# LED.net
KiCad netlist of a schematic drawn in Altium Designer
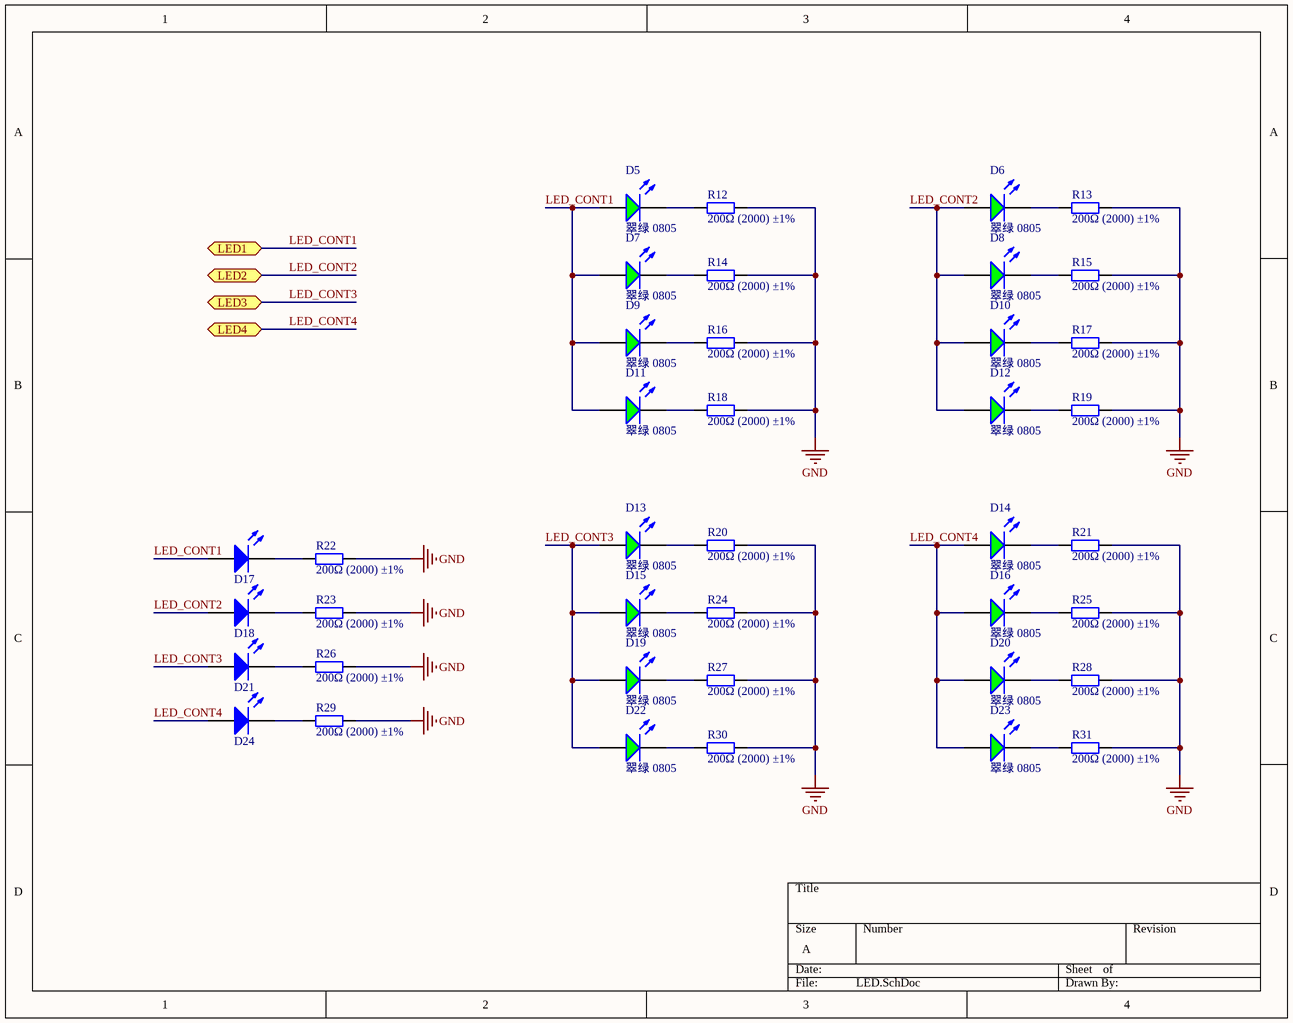
[diagram p0: LED.SchDoc]

(export (version "E")
  (design (tool "Eeschema 10.0.6"))
  (components
    (comp (ref "D5")
      (value "翠绿 0805")
      (footprint "LC-0805_LED_S1")
      (description "发光二极管")
      (libsource (lib "Miscellaneous Devices LC") (part "0805 翠绿"))
    )
    (comp (ref "D6")
      (value "翠绿 0805")
      (footprint "LC-0805_LED_S1")
      (description "发光二极管")
      (libsource (lib "Miscellaneous Devices LC") (part "0805 翠绿"))
    )
    (comp (ref "D7")
      (value "翠绿 0805")
      (footprint "LC-0805_LED_S1")
      (description "发光二极管")
      (libsource (lib "Miscellaneous Devices LC") (part "0805 翠绿"))
    )
    (comp (ref "D8")
      (value "翠绿 0805")
      (footprint "LC-0805_LED_S1")
      (description "发光二极管")
      (libsource (lib "Miscellaneous Devices LC") (part "0805 翠绿"))
    )
    (comp (ref "D9")
      (value "翠绿 0805")
      (footprint "LC-0805_LED_S1")
      (description "发光二极管")
      (libsource (lib "Miscellaneous Devices LC") (part "0805 翠绿"))
    )
    (comp (ref "D10")
      (value "翠绿 0805")
      (footprint "LC-0805_LED_S1")
      (description "发光二极管")
      (libsource (lib "Miscellaneous Devices LC") (part "0805 翠绿"))
    )
    (comp (ref "D11")
      (value "翠绿 0805")
      (footprint "LC-0805_LED_S1")
      (description "发光二极管")
      (libsource (lib "Miscellaneous Devices LC") (part "0805 翠绿"))
    )
    (comp (ref "D12")
      (value "翠绿 0805")
      (footprint "LC-0805_LED_S1")
      (description "发光二极管")
      (libsource (lib "Miscellaneous Devices LC") (part "0805 翠绿"))
    )
    (comp (ref "D13")
      (value "翠绿 0805")
      (footprint "LC-0805_LED_S1")
      (description "发光二极管")
      (libsource (lib "Miscellaneous Devices LC") (part "0805 翠绿"))
    )
    (comp (ref "D14")
      (value "翠绿 0805")
      (footprint "LC-0805_LED_S1")
      (description "发光二极管")
      (libsource (lib "Miscellaneous Devices LC") (part "0805 翠绿"))
    )
    (comp (ref "D15")
      (value "翠绿 0805")
      (footprint "LC-0805_LED_S1")
      (description "发光二极管")
      (libsource (lib "Miscellaneous Devices LC") (part "0805 翠绿"))
    )
    (comp (ref "D16")
      (value "翠绿 0805")
      (footprint "LC-0805_LED_S1")
      (description "发光二极管")
      (libsource (lib "Miscellaneous Devices LC") (part "0805 翠绿"))
    )
    (comp (ref "D17")
      (value "LED0")
      (footprint "LED_A2")
      (description "发光二极管")
      (fields (field (name "PUBLISHER") "Altium Limited"))
      (libsource (lib "Fszhang") (part "LED0"))
    )
    (comp (ref "D18")
      (value "LED0")
      (footprint "LED_A2")
      (description "发光二极管")
      (fields (field (name "PUBLISHER") "Altium Limited"))
      (libsource (lib "Fszhang") (part "LED0"))
    )
    (comp (ref "D19")
      (value "翠绿 0805")
      (footprint "LC-0805_LED_S1")
      (description "发光二极管")
      (libsource (lib "Miscellaneous Devices LC") (part "0805 翠绿"))
    )
    (comp (ref "D20")
      (value "翠绿 0805")
      (footprint "LC-0805_LED_S1")
      (description "发光二极管")
      (libsource (lib "Miscellaneous Devices LC") (part "0805 翠绿"))
    )
    (comp (ref "D21")
      (value "LED0")
      (footprint "LED_A2")
      (description "发光二极管")
      (fields (field (name "PUBLISHER") "Altium Limited"))
      (libsource (lib "Fszhang") (part "LED0"))
    )
    (comp (ref "D22")
      (value "翠绿 0805")
      (footprint "LC-0805_LED_S1")
      (description "发光二极管")
      (libsource (lib "Miscellaneous Devices LC") (part "0805 翠绿"))
    )
    (comp (ref "D23")
      (value "翠绿 0805")
      (footprint "LC-0805_LED_S1")
      (description "发光二极管")
      (libsource (lib "Miscellaneous Devices LC") (part "0805 翠绿"))
    )
    (comp (ref "D24")
      (value "LED0")
      (footprint "LED_A2")
      (description "发光二极管")
      (fields (field (name "PUBLISHER") "Altium Limited"))
      (libsource (lib "Fszhang") (part "LED0"))
    )
    (comp (ref "R12")
      (value "200Ω (2000) ±1%")
      (footprint "LC-0805_R")
      (description "贴片电阻")
      (libsource (lib "Miscellaneous Devices LC") (part "0805 200Ω (2000) 1%"))
    )
    (comp (ref "R13")
      (value "200Ω (2000) ±1%")
      (footprint "LC-0805_R")
      (description "贴片电阻")
      (libsource (lib "Miscellaneous Devices LC") (part "0805 200Ω (2000) 1%"))
    )
    (comp (ref "R14")
      (value "200Ω (2000) ±1%")
      (footprint "LC-0805_R")
      (description "贴片电阻")
      (libsource (lib "Miscellaneous Devices LC") (part "0805 200Ω (2000) 1%"))
    )
    (comp (ref "R15")
      (value "200Ω (2000) ±1%")
      (footprint "LC-0805_R")
      (description "贴片电阻")
      (libsource (lib "Miscellaneous Devices LC") (part "0805 200Ω (2000) 1%"))
    )
    (comp (ref "R16")
      (value "200Ω (2000) ±1%")
      (footprint "LC-0805_R")
      (description "贴片电阻")
      (libsource (lib "Miscellaneous Devices LC") (part "0805 200Ω (2000) 1%"))
    )
    (comp (ref "R17")
      (value "200Ω (2000) ±1%")
      (footprint "LC-0805_R")
      (description "贴片电阻")
      (libsource (lib "Miscellaneous Devices LC") (part "0805 200Ω (2000) 1%"))
    )
    (comp (ref "R18")
      (value "200Ω (2000) ±1%")
      (footprint "LC-0805_R")
      (description "贴片电阻")
      (libsource (lib "Miscellaneous Devices LC") (part "0805 200Ω (2000) 1%"))
    )
    (comp (ref "R19")
      (value "200Ω (2000) ±1%")
      (footprint "LC-0805_R")
      (description "贴片电阻")
      (libsource (lib "Miscellaneous Devices LC") (part "0805 200Ω (2000) 1%"))
    )
    (comp (ref "R20")
      (value "200Ω (2000) ±1%")
      (footprint "LC-0805_R")
      (description "贴片电阻")
      (libsource (lib "Miscellaneous Devices LC") (part "0805 200Ω (2000) 1%"))
    )
    (comp (ref "R21")
      (value "200Ω (2000) ±1%")
      (footprint "LC-0805_R")
      (description "贴片电阻")
      (libsource (lib "Miscellaneous Devices LC") (part "0805 200Ω (2000) 1%"))
    )
    (comp (ref "R22")
      (value "200Ω (2000) ±1%")
      (footprint "LC-0805_R")
      (description "贴片电阻")
      (libsource (lib "Miscellaneous Devices LC") (part "0805 200Ω (2000) 1%"))
    )
    (comp (ref "R23")
      (value "200Ω (2000) ±1%")
      (footprint "LC-0805_R")
      (description "贴片电阻")
      (libsource (lib "Miscellaneous Devices LC") (part "0805 200Ω (2000) 1%"))
    )
    (comp (ref "R24")
      (value "200Ω (2000) ±1%")
      (footprint "LC-0805_R")
      (description "贴片电阻")
      (libsource (lib "Miscellaneous Devices LC") (part "0805 200Ω (2000) 1%"))
    )
    (comp (ref "R25")
      (value "200Ω (2000) ±1%")
      (footprint "LC-0805_R")
      (description "贴片电阻")
      (libsource (lib "Miscellaneous Devices LC") (part "0805 200Ω (2000) 1%"))
    )
    (comp (ref "R26")
      (value "200Ω (2000) ±1%")
      (footprint "LC-0805_R")
      (description "贴片电阻")
      (libsource (lib "Miscellaneous Devices LC") (part "0805 200Ω (2000) 1%"))
    )
    (comp (ref "R27")
      (value "200Ω (2000) ±1%")
      (footprint "LC-0805_R")
      (description "贴片电阻")
      (libsource (lib "Miscellaneous Devices LC") (part "0805 200Ω (2000) 1%"))
    )
    (comp (ref "R28")
      (value "200Ω (2000) ±1%")
      (footprint "LC-0805_R")
      (description "贴片电阻")
      (libsource (lib "Miscellaneous Devices LC") (part "0805 200Ω (2000) 1%"))
    )
    (comp (ref "R29")
      (value "200Ω (2000) ±1%")
      (footprint "LC-0805_R")
      (description "贴片电阻")
      (libsource (lib "Miscellaneous Devices LC") (part "0805 200Ω (2000) 1%"))
    )
    (comp (ref "R30")
      (value "200Ω (2000) ±1%")
      (footprint "LC-0805_R")
      (description "贴片电阻")
      (libsource (lib "Miscellaneous Devices LC") (part "0805 200Ω (2000) 1%"))
    )
    (comp (ref "R31")
      (value "200Ω (2000) ±1%")
      (footprint "LC-0805_R")
      (description "贴片电阻")
      (libsource (lib "Miscellaneous Devices LC") (part "0805 200Ω (2000) 1%"))
    )
  )
  (nets
    (net (code "1") (name "/LED_CONT1") (class "Default")
      (node (ref "D11") (pin "A") (pinfunction "A_A") (pintype "passive"))
      (node (ref "D17") (pin "1") (pinfunction "A_1") (pintype "passive"))
      (node (ref "D5") (pin "A") (pinfunction "A_A") (pintype "passive"))
      (node (ref "D7") (pin "A") (pinfunction "A_A") (pintype "passive"))
      (node (ref "D9") (pin "A") (pinfunction "A_A") (pintype "passive"))
    )
    (net (code "2") (name "/LED_CONT2") (class "Default")
      (node (ref "D10") (pin "A") (pinfunction "A_A") (pintype "passive"))
      (node (ref "D12") (pin "A") (pinfunction "A_A") (pintype "passive"))
      (node (ref "D18") (pin "1") (pinfunction "A_1") (pintype "passive"))
      (node (ref "D6") (pin "A") (pinfunction "A_A") (pintype "passive"))
      (node (ref "D8") (pin "A") (pinfunction "A_A") (pintype "passive"))
    )
    (net (code "3") (name "/LED_CONT3") (class "Default")
      (node (ref "D13") (pin "A") (pinfunction "A_A") (pintype "passive"))
      (node (ref "D15") (pin "A") (pinfunction "A_A") (pintype "passive"))
      (node (ref "D19") (pin "A") (pinfunction "A_A") (pintype "passive"))
      (node (ref "D21") (pin "1") (pinfunction "A_1") (pintype "passive"))
      (node (ref "D22") (pin "A") (pinfunction "A_A") (pintype "passive"))
    )
    (net (code "4") (name "/LED_CONT4") (class "Default")
      (node (ref "D14") (pin "A") (pinfunction "A_A") (pintype "passive"))
      (node (ref "D16") (pin "A") (pinfunction "A_A") (pintype "passive"))
      (node (ref "D20") (pin "A") (pinfunction "A_A") (pintype "passive"))
      (node (ref "D23") (pin "A") (pinfunction "A_A") (pintype "passive"))
      (node (ref "D24") (pin "1") (pinfunction "A_1") (pintype "passive"))
    )
    (net (code "5") (name "GND") (class "Default")
      (node (ref "R12") (pin "2") (pinfunction "2_2") (pintype "passive"))
      (node (ref "R13") (pin "2") (pinfunction "2_2") (pintype "passive"))
      (node (ref "R14") (pin "2") (pinfunction "2_2") (pintype "passive"))
      (node (ref "R15") (pin "2") (pinfunction "2_2") (pintype "passive"))
      (node (ref "R16") (pin "2") (pinfunction "2_2") (pintype "passive"))
      (node (ref "R17") (pin "2") (pinfunction "2_2") (pintype "passive"))
      (node (ref "R18") (pin "2") (pinfunction "2_2") (pintype "passive"))
      (node (ref "R19") (pin "2") (pinfunction "2_2") (pintype "passive"))
      (node (ref "R20") (pin "2") (pinfunction "2_2") (pintype "passive"))
      (node (ref "R21") (pin "2") (pinfunction "2_2") (pintype "passive"))
      (node (ref "R22") (pin "2") (pinfunction "2_2") (pintype "passive"))
      (node (ref "R23") (pin "2") (pinfunction "2_2") (pintype "passive"))
      (node (ref "R24") (pin "2") (pinfunction "2_2") (pintype "passive"))
      (node (ref "R25") (pin "2") (pinfunction "2_2") (pintype "passive"))
      (node (ref "R26") (pin "2") (pinfunction "2_2") (pintype "passive"))
      (node (ref "R27") (pin "2") (pinfunction "2_2") (pintype "passive"))
      (node (ref "R28") (pin "2") (pinfunction "2_2") (pintype "passive"))
      (node (ref "R29") (pin "2") (pinfunction "2_2") (pintype "passive"))
      (node (ref "R30") (pin "2") (pinfunction "2_2") (pintype "passive"))
      (node (ref "R31") (pin "2") (pinfunction "2_2") (pintype "passive"))
    )
    (net (code "6") (name "Net-(D5-PadK)") (class "Default")
      (node (ref "D5") (pin "K") (pinfunction "K_K") (pintype "passive"))
      (node (ref "R12") (pin "1") (pinfunction "1_1") (pintype "passive"))
    )
    (net (code "7") (name "Net-(D6-PadK)") (class "Default")
      (node (ref "D6") (pin "K") (pinfunction "K_K") (pintype "passive"))
      (node (ref "R13") (pin "1") (pinfunction "1_1") (pintype "passive"))
    )
    (net (code "8") (name "Net-(D7-PadK)") (class "Default")
      (node (ref "D7") (pin "K") (pinfunction "K_K") (pintype "passive"))
      (node (ref "R14") (pin "1") (pinfunction "1_1") (pintype "passive"))
    )
    (net (code "9") (name "Net-(D8-PadK)") (class "Default")
      (node (ref "D8") (pin "K") (pinfunction "K_K") (pintype "passive"))
      (node (ref "R15") (pin "1") (pinfunction "1_1") (pintype "passive"))
    )
    (net (code "10") (name "Net-(D9-PadK)") (class "Default")
      (node (ref "D9") (pin "K") (pinfunction "K_K") (pintype "passive"))
      (node (ref "R16") (pin "1") (pinfunction "1_1") (pintype "passive"))
    )
    (net (code "11") (name "Net-(D10-PadK)") (class "Default")
      (node (ref "D10") (pin "K") (pinfunction "K_K") (pintype "passive"))
      (node (ref "R17") (pin "1") (pinfunction "1_1") (pintype "passive"))
    )
    (net (code "12") (name "Net-(D11-PadK)") (class "Default")
      (node (ref "D11") (pin "K") (pinfunction "K_K") (pintype "passive"))
      (node (ref "R18") (pin "1") (pinfunction "1_1") (pintype "passive"))
    )
    (net (code "13") (name "Net-(D12-PadK)") (class "Default")
      (node (ref "D12") (pin "K") (pinfunction "K_K") (pintype "passive"))
      (node (ref "R19") (pin "1") (pinfunction "1_1") (pintype "passive"))
    )
    (net (code "14") (name "Net-(D13-PadK)") (class "Default")
      (node (ref "D13") (pin "K") (pinfunction "K_K") (pintype "passive"))
      (node (ref "R20") (pin "1") (pinfunction "1_1") (pintype "passive"))
    )
    (net (code "15") (name "Net-(D14-PadK)") (class "Default")
      (node (ref "D14") (pin "K") (pinfunction "K_K") (pintype "passive"))
      (node (ref "R21") (pin "1") (pinfunction "1_1") (pintype "passive"))
    )
    (net (code "16") (name "Net-(D15-PadK)") (class "Default")
      (node (ref "D15") (pin "K") (pinfunction "K_K") (pintype "passive"))
      (node (ref "R24") (pin "1") (pinfunction "1_1") (pintype "passive"))
    )
    (net (code "17") (name "Net-(D16-PadK)") (class "Default")
      (node (ref "D16") (pin "K") (pinfunction "K_K") (pintype "passive"))
      (node (ref "R25") (pin "1") (pinfunction "1_1") (pintype "passive"))
    )
    (net (code "18") (name "Net-(D17-K)") (class "Default")
      (node (ref "D17") (pin "2") (pinfunction "K_2") (pintype "passive"))
      (node (ref "R22") (pin "1") (pinfunction "1_1") (pintype "passive"))
    )
    (net (code "19") (name "Net-(D18-K)") (class "Default")
      (node (ref "D18") (pin "2") (pinfunction "K_2") (pintype "passive"))
      (node (ref "R23") (pin "1") (pinfunction "1_1") (pintype "passive"))
    )
    (net (code "20") (name "Net-(D19-PadK)") (class "Default")
      (node (ref "D19") (pin "K") (pinfunction "K_K") (pintype "passive"))
      (node (ref "R27") (pin "1") (pinfunction "1_1") (pintype "passive"))
    )
    (net (code "21") (name "Net-(D20-PadK)") (class "Default")
      (node (ref "D20") (pin "K") (pinfunction "K_K") (pintype "passive"))
      (node (ref "R28") (pin "1") (pinfunction "1_1") (pintype "passive"))
    )
    (net (code "22") (name "Net-(D21-K)") (class "Default")
      (node (ref "D21") (pin "2") (pinfunction "K_2") (pintype "passive"))
      (node (ref "R26") (pin "1") (pinfunction "1_1") (pintype "passive"))
    )
    (net (code "23") (name "Net-(D22-PadK)") (class "Default")
      (node (ref "D22") (pin "K") (pinfunction "K_K") (pintype "passive"))
      (node (ref "R30") (pin "1") (pinfunction "1_1") (pintype "passive"))
    )
    (net (code "24") (name "Net-(D23-PadK)") (class "Default")
      (node (ref "D23") (pin "K") (pinfunction "K_K") (pintype "passive"))
      (node (ref "R31") (pin "1") (pinfunction "1_1") (pintype "passive"))
    )
    (net (code "25") (name "Net-(D24-K)") (class "Default")
      (node (ref "D24") (pin "2") (pinfunction "K_2") (pintype "passive"))
      (node (ref "R29") (pin "1") (pinfunction "1_1") (pintype "passive"))
    )
  )
)
